# nbiot_gps.net
KiCad netlist of a schematic drawn in Altium Designer
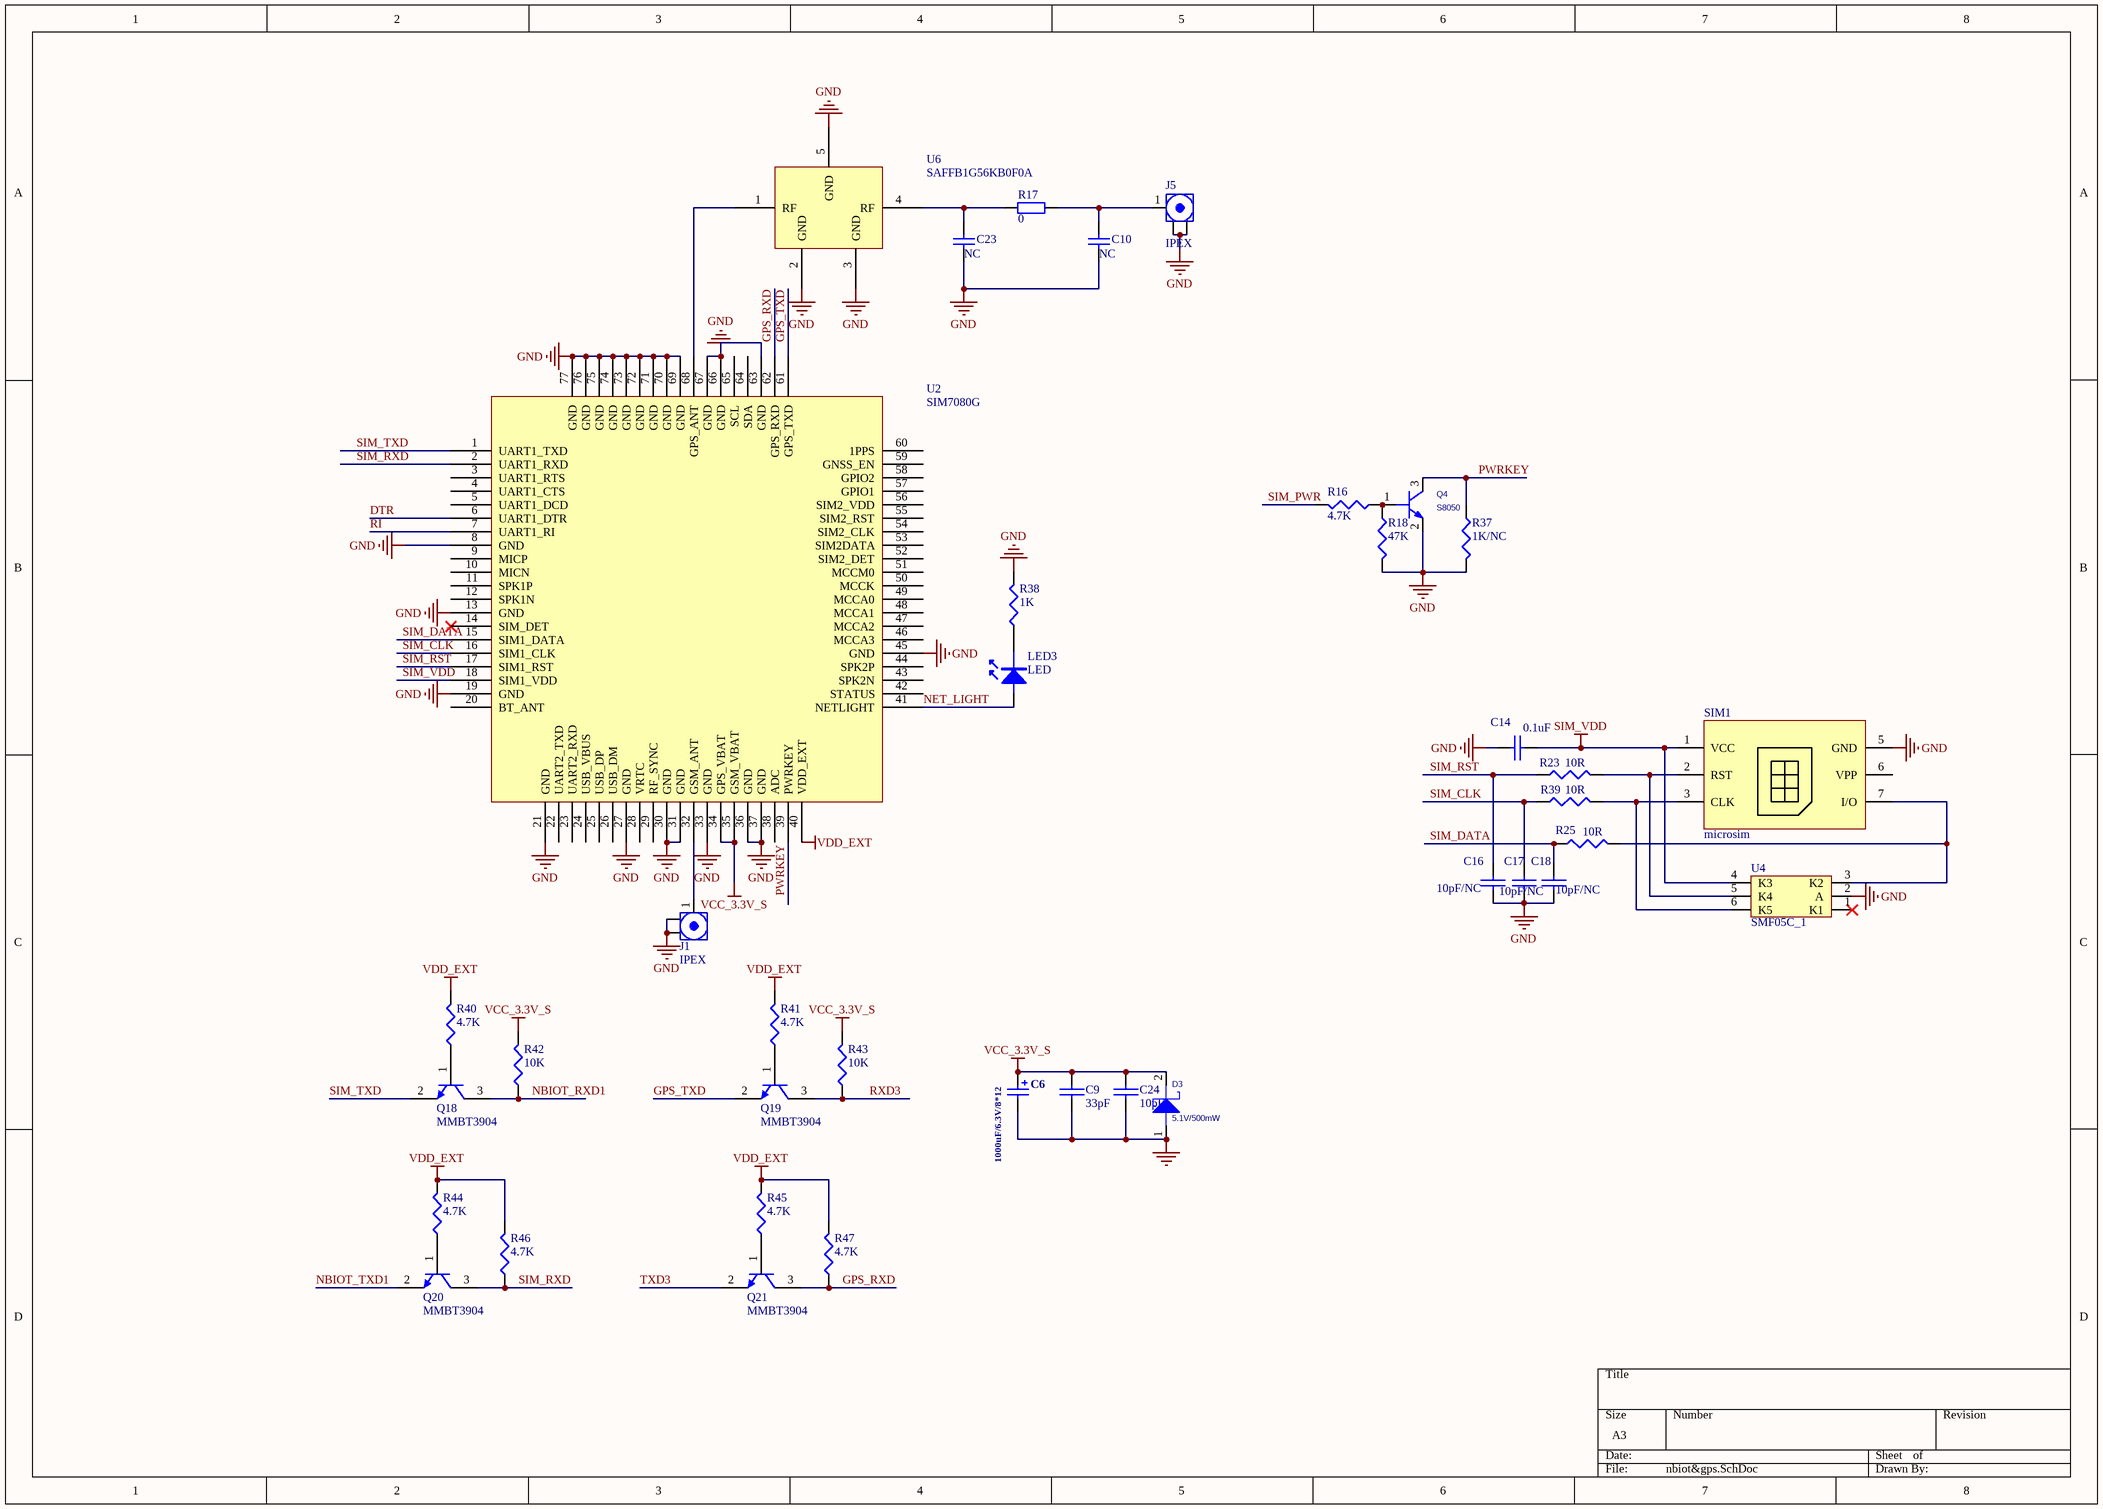
[diagram p0: nbiot&gps.SchDoc]

(export (version "E")
  (design (tool "Eeschema 10.0.6"))
  (components
    (comp (ref "C6")
      (value "1000uF/6.3V/8*12")
      (footprint "8*12")
      (description "Polarized Capacitor (Surface Mount)")
      (libsource (lib "KT_iBeacon") (part "Cap Pol3"))
    )
    (comp (ref "C9")
      (value "33pF")
      (footprint "0603C")
      (description "Capacitor")
      (libsource (lib "ZWLIntegrated_Library") (part "CAP"))
    )
    (comp (ref "C10")
      (value "NC")
      (footprint "0603C")
      (description "Capacitor")
      (fields (field (name "PUBLISHER") "Altium Limited"))
      (libsource (lib "Miscellaneous Devices") (part "Cap"))
    )
    (comp (ref "C14")
      (value "0.1uF")
      (footprint "0603C")
      (description "Capacitor")
      (libsource (lib "ZWLIntegrated_Library") (part "CAP"))
    )
    (comp (ref "C16")
      (value "10pF/NC")
      (footprint "0603C")
      (description "Capacitor")
      (libsource (lib "ZWLIntegrated_Library") (part "CAP"))
    )
    (comp (ref "C17")
      (value "10pF/NC")
      (footprint "0603C")
      (description "Capacitor")
      (libsource (lib "ZWLIntegrated_Library") (part "CAP"))
    )
    (comp (ref "C18")
      (value "10pF/NC")
      (footprint "0603C")
      (description "Capacitor")
      (libsource (lib "ZWLIntegrated_Library") (part "CAP"))
    )
    (comp (ref "C23")
      (value "NC")
      (footprint "0603C")
      (description "Capacitor")
      (fields (field (name "PUBLISHER") "Altium Limited"))
      (libsource (lib "Miscellaneous Devices") (part "Cap"))
    )
    (comp (ref "C24")
      (value "10pF")
      (footprint "0603C")
      (description "Capacitor")
      (libsource (lib "ZWLIntegrated_Library") (part "CAP"))
    )
    (comp (ref "D3")
      (value "5.1V/500mW")
      (footprint "LL-34(D1206)")
      (fields (field (name "Comment") "DIODE_SCHOTTKY_0"))
      (libsource (lib "KT_iBeacon") (part "DIODE_SCHOTTKY_0"))
    )
    (comp (ref "J1") (value "IPEX") (footprint "RF-UFL") (libsource (lib "我的元件库") (part "ANT")))
    (comp (ref "J5") (value "IPEX") (footprint "RF-UFL") (libsource (lib "我的元件库") (part "ANT")))
    (comp (ref "LED3") (value "LED") (footprint "0603LED") (libsource (lib "我的元件库") (part "LED")))
    (comp (ref "Q4") (value "S8050") (footprint "SOT23") (libsource (lib "*") (part "2N1069_1")))
    (comp (ref "Q18") (value "MMBT3904") (footprint "SOT23-3") (libsource (lib "Schlib1") (part "NPN")))
    (comp (ref "Q19") (value "MMBT3904") (footprint "SOT23-3") (libsource (lib "Schlib1") (part "NPN")))
    (comp (ref "Q20") (value "MMBT3904") (footprint "SOT23-3") (libsource (lib "Schlib1") (part "NPN")))
    (comp (ref "Q21") (value "MMBT3904") (footprint "SOT23-3") (libsource (lib "Schlib1") (part "NPN")))
    (comp (ref "R16")
      (value "4.7K")
      (footprint "0603R")
      (libsource (lib "ZWLIntegrated_Library") (part "RES1"))
    )
    (comp (ref "R17")
      (value "0")
      (footprint "0603R")
      (description "Resistor")
      (fields (field (name "PUBLISHER") "Altium Limited"))
      (libsource (lib "Miscellaneous Devices") (part "Res2"))
    )
    (comp (ref "R18")
      (value "47K")
      (footprint "0603R")
      (libsource (lib "ZWLIntegrated_Library") (part "RES1"))
    )
    (comp (ref "R23")
      (value "10R")
      (footprint "0603R")
      (libsource (lib "ZWLIntegrated_Library") (part "RES1"))
    )
    (comp (ref "R25")
      (value "10R")
      (footprint "0603R")
      (libsource (lib "ZWLIntegrated_Library") (part "RES1"))
    )
    (comp (ref "R37")
      (value "1K/NC")
      (footprint "0603R")
      (libsource (lib "ZWLIntegrated_Library") (part "RES1"))
    )
    (comp (ref "R38")
      (value "1K")
      (footprint "0603R")
      (libsource (lib "ZWLIntegrated_Library") (part "RES1"))
    )
    (comp (ref "R39")
      (value "10R")
      (footprint "0603R")
      (libsource (lib "ZWLIntegrated_Library") (part "RES1"))
    )
    (comp (ref "R40")
      (value "4.7K")
      (footprint "0603R")
      (libsource (lib "ZWLIntegrated_Library") (part "RES1"))
    )
    (comp (ref "R41")
      (value "4.7K")
      (footprint "0603R")
      (libsource (lib "ZWLIntegrated_Library") (part "RES1"))
    )
    (comp (ref "R42")
      (value "10K")
      (footprint "0603R")
      (libsource (lib "ZWLIntegrated_Library") (part "RES1"))
    )
    (comp (ref "R43")
      (value "10K")
      (footprint "0603R")
      (libsource (lib "ZWLIntegrated_Library") (part "RES1"))
    )
    (comp (ref "R44")
      (value "4.7K")
      (footprint "0603R")
      (libsource (lib "ZWLIntegrated_Library") (part "RES1"))
    )
    (comp (ref "R45")
      (value "4.7K")
      (footprint "0603R")
      (libsource (lib "ZWLIntegrated_Library") (part "RES1"))
    )
    (comp (ref "R46")
      (value "4.7K")
      (footprint "0603R")
      (libsource (lib "ZWLIntegrated_Library") (part "RES1"))
    )
    (comp (ref "R47")
      (value "4.7K")
      (footprint "0603R")
      (libsource (lib "ZWLIntegrated_Library") (part "RES1"))
    )
    (comp (ref "SIM1")
      (value "microsim")
      (footprint "Nano SIM")
      (libsource (lib "SIM800C 原理图库") (part "microsim"))
    )
    (comp (ref "U2")
      (value "SIM7080G")
      (footprint "SIM868")
      (libsource (lib "stm32") (part "SIM868E/SIM868"))
    )
    (comp (ref "U4")
      (value "SMF05C_1")
      (footprint "SC70-6L")
      (description "TVS")
      (libsource (lib "SIM800C 原理图库") (part "SMF05C_1"))
    )
    (comp (ref "U6")
      (value "SAFFB1G56KB0F0A")
      (footprint "SAFFB1G56KB0F0A")
      (libsource (lib "stm32") (part "SAFFB1G56KBOFA"))
    )
  )
  (nets
    (net (code "1") (name "/DTR") (class "Default")
      (node (ref "U2") (pin "6") (pinfunction "UART1_DTR_6") (pintype "passive"))
    )
    (net (code "2") (name "/GPS_RXD") (class "Default")
      (node (ref "Q21") (pin "3") (pinfunction "C_3") (pintype "passive"))
      (node (ref "R47") (pin "1") (pinfunction "1_1") (pintype "passive"))
      (node (ref "U2") (pin "62") (pinfunction "GPS_RXD_62") (pintype "passive"))
    )
    (net (code "3") (name "/GPS_TXD") (class "Default")
      (node (ref "Q19") (pin "2") (pinfunction "E_2") (pintype "passive"))
      (node (ref "U2") (pin "61") (pinfunction "GPS_TXD_61") (pintype "passive"))
    )
    (net (code "4") (name "/NBIOT_RXD1") (class "Default")
      (node (ref "Q18") (pin "3") (pinfunction "C_3") (pintype "passive"))
      (node (ref "R42") (pin "1") (pinfunction "1_1") (pintype "passive"))
    )
    (net (code "5") (name "/NBIOT_TXD1") (class "Default")
      (node (ref "Q20") (pin "2") (pinfunction "E_2") (pintype "passive"))
    )
    (net (code "6") (name "/NET_LIGHT") (class "Default")
      (node (ref "LED3") (pin "1") (pinfunction "1_1") (pintype "passive"))
      (node (ref "U2") (pin "41") (pinfunction "NETLIGHT_41") (pintype "passive"))
    )
    (net (code "7") (name "/PWRKEY") (class "Default")
      (node (ref "Q4") (pin "3") (pinfunction "C_3") (pintype "passive"))
      (node (ref "R37") (pin "1") (pinfunction "1_1") (pintype "passive"))
      (node (ref "U2") (pin "39") (pinfunction "PWRKEY_39") (pintype "passive"))
    )
    (net (code "8") (name "/RI") (class "Default")
      (node (ref "U2") (pin "7") (pinfunction "UART1_RI_7") (pintype "passive"))
    )
    (net (code "9") (name "/RXD3") (class "Default")
      (node (ref "Q19") (pin "3") (pinfunction "C_3") (pintype "passive"))
      (node (ref "R43") (pin "1") (pinfunction "1_1") (pintype "passive"))
    )
    (net (code "10") (name "/SIM_CLK") (class "Default")
      (node (ref "C17") (pin "2") (pinfunction "2_2") (pintype "passive"))
      (node (ref "R39") (pin "1") (pinfunction "1_1") (pintype "passive"))
      (node (ref "U2") (pin "16") (pinfunction "SIM1_CLK_16") (pintype "passive"))
    )
    (net (code "11") (name "/SIM_DATA") (class "Default")
      (node (ref "C18") (pin "2") (pinfunction "2_2") (pintype "passive"))
      (node (ref "R25") (pin "1") (pinfunction "1_1") (pintype "passive"))
      (node (ref "U2") (pin "15") (pinfunction "SIM1_DATA_15") (pintype "passive"))
    )
    (net (code "12") (name "/SIM_PWR") (class "Default")
      (node (ref "R16") (pin "2") (pinfunction "2_2") (pintype "passive"))
    )
    (net (code "13") (name "/SIM_RST") (class "Default")
      (node (ref "C16") (pin "2") (pinfunction "2_2") (pintype "passive"))
      (node (ref "R23") (pin "1") (pinfunction "1_1") (pintype "passive"))
      (node (ref "U2") (pin "17") (pinfunction "SIM1_RST_17") (pintype "passive"))
    )
    (net (code "14") (name "/SIM_RXD") (class "Default")
      (node (ref "Q20") (pin "3") (pinfunction "C_3") (pintype "passive"))
      (node (ref "R46") (pin "1") (pinfunction "1_1") (pintype "passive"))
      (node (ref "U2") (pin "2") (pinfunction "UART1_RXD_2") (pintype "passive"))
    )
    (net (code "15") (name "/SIM_TXD") (class "Default")
      (node (ref "Q18") (pin "2") (pinfunction "E_2") (pintype "passive"))
      (node (ref "U2") (pin "1") (pinfunction "UART1_TXD_1") (pintype "passive"))
    )
    (net (code "16") (name "/TXD3") (class "Default")
      (node (ref "Q21") (pin "2") (pinfunction "E_2") (pintype "passive"))
    )
    (net (code "17") (name "GND") (class "Default")
      (node (ref "C10") (pin "2") (pinfunction "2_2") (pintype "passive"))
      (node (ref "C14") (pin "1") (pinfunction "1_1") (pintype "passive"))
      (node (ref "C16") (pin "1") (pinfunction "1_1") (pintype "passive"))
      (node (ref "C17") (pin "1") (pinfunction "1_1") (pintype "passive"))
      (node (ref "C18") (pin "1") (pinfunction "1_1") (pintype "passive"))
      (node (ref "C23") (pin "2") (pinfunction "2_2") (pintype "passive"))
      (node (ref "C24") (pin "1") (pinfunction "1_1") (pintype "passive"))
      (node (ref "C6") (pin "2") (pinfunction "2_2") (pintype "passive"))
      (node (ref "C9") (pin "1") (pinfunction "1_1") (pintype "passive"))
      (node (ref "D3") (pin "1") (pinfunction "1_1") (pintype "passive"))
      (node (ref "J1") (pin "2") (pinfunction "Y_2") (pintype "passive"))
      (node (ref "J5") (pin "2") (pinfunction "Y_2") (pintype "passive"))
      (node (ref "Q4") (pin "2") (pinfunction "E_2") (pintype "passive"))
      (node (ref "R18") (pin "2") (pinfunction "2_2") (pintype "passive"))
      (node (ref "R37") (pin "2") (pinfunction "2_2") (pintype "passive"))
      (node (ref "R38") (pin "2") (pinfunction "2_2") (pintype "passive"))
      (node (ref "SIM1") (pin "5") (pinfunction "GND_5") (pintype "passive"))
      (node (ref "U2") (pin "13") (pinfunction "GND_13") (pintype "passive"))
      (node (ref "U2") (pin "19") (pinfunction "GND_19") (pintype "passive"))
      (node (ref "U2") (pin "21") (pinfunction "GND_21") (pintype "passive"))
      (node (ref "U2") (pin "27") (pinfunction "GND_27") (pintype "passive"))
      (node (ref "U2") (pin "30") (pinfunction "GND_30") (pintype "passive"))
      (node (ref "U2") (pin "31") (pinfunction "GND_31") (pintype "passive"))
      (node (ref "U2") (pin "33") (pinfunction "GND_33") (pintype "passive"))
      (node (ref "U2") (pin "36") (pinfunction "GND_36") (pintype "passive"))
      (node (ref "U2") (pin "37") (pinfunction "GND_37") (pintype "passive"))
      (node (ref "U2") (pin "45") (pinfunction "GND_45") (pintype "passive"))
      (node (ref "U2") (pin "63") (pinfunction "GND_63") (pintype "passive"))
      (node (ref "U2") (pin "66") (pinfunction "GND_66") (pintype "passive"))
      (node (ref "U2") (pin "67") (pinfunction "GND_67") (pintype "passive"))
      (node (ref "U2") (pin "69") (pinfunction "GND_69") (pintype "passive"))
      (node (ref "U2") (pin "70") (pinfunction "GND_70") (pintype "passive"))
      (node (ref "U2") (pin "71") (pinfunction "GND_71") (pintype "passive"))
      (node (ref "U2") (pin "72") (pinfunction "GND_72") (pintype "passive"))
      (node (ref "U2") (pin "73") (pinfunction "GND_73") (pintype "passive"))
      (node (ref "U2") (pin "74") (pinfunction "GND_74") (pintype "passive"))
      (node (ref "U2") (pin "75") (pinfunction "GND_75") (pintype "passive"))
      (node (ref "U2") (pin "76") (pinfunction "GND_76") (pintype "passive"))
      (node (ref "U2") (pin "77") (pinfunction "GND_77") (pintype "passive"))
      (node (ref "U2") (pin "8") (pinfunction "GND_8") (pintype "passive"))
      (node (ref "U4") (pin "2") (pinfunction "A_2") (pintype "passive"))
      (node (ref "U6") (pin "2") (pinfunction "GND_2") (pintype "passive"))
      (node (ref "U6") (pin "3") (pinfunction "GND_3") (pintype "passive"))
      (node (ref "U6") (pin "5") (pinfunction "GND_5") (pintype "passive"))
    )
    (net (code "18") (name "Net-(C23-Pad1)") (class "Default")
      (node (ref "C23") (pin "1") (pinfunction "1_1") (pintype "passive"))
      (node (ref "R17") (pin "1") (pinfunction "1_1") (pintype "passive"))
      (node (ref "U6") (pin "4") (pinfunction "RF_4") (pintype "passive"))
    )
    (net (code "19") (name "Net-(J1-X)") (class "Default")
      (node (ref "J1") (pin "1") (pinfunction "X_1") (pintype "passive"))
      (node (ref "U2") (pin "32") (pinfunction "GSM_ANT_32") (pintype "passive"))
    )
    (net (code "20") (name "Net-(J5-X)") (class "Default")
      (node (ref "C10") (pin "1") (pinfunction "1_1") (pintype "passive"))
      (node (ref "J5") (pin "1") (pinfunction "X_1") (pintype "passive"))
      (node (ref "R17") (pin "2") (pinfunction "2_2") (pintype "passive"))
    )
    (net (code "21") (name "Net-(LED3-Pad2)") (class "Default")
      (node (ref "LED3") (pin "2") (pinfunction "2_2") (pintype "passive"))
      (node (ref "R38") (pin "1") (pinfunction "1_1") (pintype "passive"))
    )
    (net (code "22") (name "Net-(Q4-B)") (class "Default")
      (node (ref "Q4") (pin "1") (pinfunction "B_1") (pintype "passive"))
      (node (ref "R16") (pin "1") (pinfunction "1_1") (pintype "passive"))
      (node (ref "R18") (pin "1") (pinfunction "1_1") (pintype "passive"))
    )
    (net (code "23") (name "Net-(Q18-B)") (class "Default")
      (node (ref "Q18") (pin "1") (pinfunction "B_1") (pintype "passive"))
      (node (ref "R40") (pin "1") (pinfunction "1_1") (pintype "passive"))
    )
    (net (code "24") (name "Net-(Q19-B)") (class "Default")
      (node (ref "Q19") (pin "1") (pinfunction "B_1") (pintype "passive"))
      (node (ref "R41") (pin "1") (pinfunction "1_1") (pintype "passive"))
    )
    (net (code "25") (name "Net-(Q20-B)") (class "Default")
      (node (ref "Q20") (pin "1") (pinfunction "B_1") (pintype "passive"))
      (node (ref "R44") (pin "1") (pinfunction "1_1") (pintype "passive"))
    )
    (net (code "26") (name "Net-(Q21-B)") (class "Default")
      (node (ref "Q21") (pin "1") (pinfunction "B_1") (pintype "passive"))
      (node (ref "R45") (pin "1") (pinfunction "1_1") (pintype "passive"))
    )
    (net (code "27") (name "Net-(SIM1-CLK)") (class "Default")
      (node (ref "R39") (pin "2") (pinfunction "2_2") (pintype "passive"))
      (node (ref "SIM1") (pin "3") (pinfunction "CLK_3") (pintype "passive"))
      (node (ref "U4") (pin "6") (pinfunction "K5_6") (pintype "passive"))
    )
    (net (code "28") (name "Net-(SIM1-I{slash}O)") (class "Default")
      (node (ref "R25") (pin "2") (pinfunction "2_2") (pintype "passive"))
      (node (ref "SIM1") (pin "7") (pinfunction "I/O_7") (pintype "passive"))
      (node (ref "U4") (pin "3") (pinfunction "K2_3") (pintype "passive"))
    )
    (net (code "29") (name "Net-(SIM1-RST)") (class "Default")
      (node (ref "R23") (pin "2") (pinfunction "2_2") (pintype "passive"))
      (node (ref "SIM1") (pin "2") (pinfunction "RST_2") (pintype "passive"))
      (node (ref "U4") (pin "5") (pinfunction "K4_5") (pintype "passive"))
    )
    (net (code "30") (name "Net-(U2-GPS_ANT)") (class "Default")
      (node (ref "U2") (pin "68") (pinfunction "GPS_ANT_68") (pintype "passive"))
      (node (ref "U6") (pin "1") (pinfunction "RF_1") (pintype "passive"))
    )
    (net (code "31") (name "SIM_VDD") (class "Default")
      (node (ref "C14") (pin "2") (pinfunction "2_2") (pintype "passive"))
      (node (ref "SIM1") (pin "1") (pinfunction "VCC_1") (pintype "passive"))
      (node (ref "U2") (pin "18") (pinfunction "SIM1_VDD_18") (pintype "passive"))
      (node (ref "U4") (pin "4") (pinfunction "K3_4") (pintype "passive"))
    )
    (net (code "32") (name "VCC_3.3V_S") (class "Default")
      (node (ref "C24") (pin "2") (pinfunction "2_2") (pintype "passive"))
      (node (ref "C6") (pin "1") (pinfunction "1_1") (pintype "passive"))
      (node (ref "C9") (pin "2") (pinfunction "2_2") (pintype "passive"))
      (node (ref "D3") (pin "2") (pinfunction "2_2") (pintype "passive"))
      (node (ref "R42") (pin "2") (pinfunction "2_2") (pintype "passive"))
      (node (ref "R43") (pin "2") (pinfunction "2_2") (pintype "passive"))
      (node (ref "U2") (pin "34") (pinfunction "GPS_VBAT_34") (pintype "passive"))
      (node (ref "U2") (pin "35") (pinfunction "GSM_VBAT_35") (pintype "passive"))
    )
    (net (code "33") (name "VDD_EXT") (class "Default")
      (node (ref "R40") (pin "2") (pinfunction "2_2") (pintype "passive"))
      (node (ref "R41") (pin "2") (pinfunction "2_2") (pintype "passive"))
      (node (ref "R44") (pin "2") (pinfunction "2_2") (pintype "passive"))
      (node (ref "R45") (pin "2") (pinfunction "2_2") (pintype "passive"))
      (node (ref "R46") (pin "2") (pinfunction "2_2") (pintype "passive"))
      (node (ref "R47") (pin "2") (pinfunction "2_2") (pintype "passive"))
      (node (ref "U2") (pin "40") (pinfunction "VDD_EXT_40") (pintype "passive"))
    )
    (net (code "34") (name "unconnected-(SIM1-VPP-Pad6)") (class "Default")
      (node (ref "SIM1") (pin "6") (pinfunction "VPP_6") (pintype "passive"))
    )
    (net (code "35") (name "unconnected-(U2-1PPS-Pad60)") (class "Default")
      (node (ref "U2") (pin "60") (pinfunction "1PPS_60") (pintype "passive"))
    )
    (net (code "36") (name "unconnected-(U2-ADC-Pad38)") (class "Default")
      (node (ref "U2") (pin "38") (pinfunction "ADC_38") (pintype "passive"))
    )
    (net (code "37") (name "unconnected-(U2-BT_ANT-Pad20)") (class "Default")
      (node (ref "U2") (pin "20") (pinfunction "BT_ANT_20") (pintype "passive"))
    )
    (net (code "38") (name "unconnected-(U2-GNSS_EN-Pad59)") (class "Default")
      (node (ref "U2") (pin "59") (pinfunction "GNSS_EN_59") (pintype "passive"))
    )
    (net (code "39") (name "unconnected-(U2-GPIO1-Pad57)") (class "Default")
      (node (ref "U2") (pin "57") (pinfunction "GPIO1_57") (pintype "passive"))
    )
    (net (code "40") (name "unconnected-(U2-GPIO2-Pad58)") (class "Default")
      (node (ref "U2") (pin "58") (pinfunction "GPIO2_58") (pintype "passive"))
    )
    (net (code "41") (name "unconnected-(U2-MCCA0-Pad49)") (class "Default")
      (node (ref "U2") (pin "49") (pinfunction "MCCA0_49") (pintype "passive"))
    )
    (net (code "42") (name "unconnected-(U2-MCCA1-Pad48)") (class "Default")
      (node (ref "U2") (pin "48") (pinfunction "MCCA1_48") (pintype "passive"))
    )
    (net (code "43") (name "unconnected-(U2-MCCA2-Pad47)") (class "Default")
      (node (ref "U2") (pin "47") (pinfunction "MCCA2_47") (pintype "passive"))
    )
    (net (code "44") (name "unconnected-(U2-MCCA3-Pad46)") (class "Default")
      (node (ref "U2") (pin "46") (pinfunction "MCCA3_46") (pintype "passive"))
    )
    (net (code "45") (name "unconnected-(U2-MCCK-Pad50)") (class "Default")
      (node (ref "U2") (pin "50") (pinfunction "MCCK_50") (pintype "passive"))
    )
    (net (code "46") (name "unconnected-(U2-MCCM0-Pad51)") (class "Default")
      (node (ref "U2") (pin "51") (pinfunction "MCCM0_51") (pintype "passive"))
    )
    (net (code "47") (name "unconnected-(U2-MICN-Pad10)") (class "Default")
      (node (ref "U2") (pin "10") (pinfunction "MICN_10") (pintype "passive"))
    )
    (net (code "48") (name "unconnected-(U2-MICP-Pad9)") (class "Default")
      (node (ref "U2") (pin "9") (pinfunction "MICP_9") (pintype "passive"))
    )
    (net (code "49") (name "unconnected-(U2-RF_SYNC-Pad29)") (class "Default")
      (node (ref "U2") (pin "29") (pinfunction "RF_SYNC_29") (pintype "passive"))
    )
    (net (code "50") (name "unconnected-(U2-SCL-Pad65)") (class "Default")
      (node (ref "U2") (pin "65") (pinfunction "SCL_65") (pintype "passive"))
    )
    (net (code "51") (name "unconnected-(U2-SDA-Pad64)") (class "Default")
      (node (ref "U2") (pin "64") (pinfunction "SDA_64") (pintype "passive"))
    )
    (net (code "52") (name "unconnected-(U2-SIM2DATA-Pad53)") (class "Default")
      (node (ref "U2") (pin "53") (pinfunction "SIM2DATA_53") (pintype "passive"))
    )
    (net (code "53") (name "unconnected-(U2-SIM2_CLK-Pad54)") (class "Default")
      (node (ref "U2") (pin "54") (pinfunction "SIM2_CLK_54") (pintype "passive"))
    )
    (net (code "54") (name "unconnected-(U2-SIM2_DET-Pad52)") (class "Default")
      (node (ref "U2") (pin "52") (pinfunction "SIM2_DET_52") (pintype "passive"))
    )
    (net (code "55") (name "unconnected-(U2-SIM2_RST-Pad55)") (class "Default")
      (node (ref "U2") (pin "55") (pinfunction "SIM2_RST_55") (pintype "passive"))
    )
    (net (code "56") (name "unconnected-(U2-SIM2_VDD-Pad56)") (class "Default")
      (node (ref "U2") (pin "56") (pinfunction "SIM2_VDD_56") (pintype "passive"))
    )
    (net (code "57") (name "unconnected-(U2-SIM_DET-Pad14)") (class "Default")
      (node (ref "U2") (pin "14") (pinfunction "SIM_DET_14") (pintype "passive+no_connect"))
    )
    (net (code "58") (name "unconnected-(U2-SPK1N-Pad12)") (class "Default")
      (node (ref "U2") (pin "12") (pinfunction "SPK1N_12") (pintype "passive"))
    )
    (net (code "59") (name "unconnected-(U2-SPK1P-Pad11)") (class "Default")
      (node (ref "U2") (pin "11") (pinfunction "SPK1P_11") (pintype "passive"))
    )
    (net (code "60") (name "unconnected-(U2-SPK2N-Pad43)") (class "Default")
      (node (ref "U2") (pin "43") (pinfunction "SPK2N_43") (pintype "passive"))
    )
    (net (code "61") (name "unconnected-(U2-SPK2P-Pad44)") (class "Default")
      (node (ref "U2") (pin "44") (pinfunction "SPK2P_44") (pintype "passive"))
    )
    (net (code "62") (name "unconnected-(U2-STATUS-Pad42)") (class "Default")
      (node (ref "U2") (pin "42") (pinfunction "STATUS_42") (pintype "passive"))
    )
    (net (code "63") (name "unconnected-(U2-UART1_CTS-Pad4)") (class "Default")
      (node (ref "U2") (pin "4") (pinfunction "UART1_CTS_4") (pintype "passive"))
    )
    (net (code "64") (name "unconnected-(U2-UART1_DCD-Pad5)") (class "Default")
      (node (ref "U2") (pin "5") (pinfunction "UART1_DCD_5") (pintype "passive"))
    )
    (net (code "65") (name "unconnected-(U2-UART1_RTS-Pad3)") (class "Default")
      (node (ref "U2") (pin "3") (pinfunction "UART1_RTS_3") (pintype "passive"))
    )
    (net (code "66") (name "unconnected-(U2-UART2_RXD-Pad23)") (class "Default")
      (node (ref "U2") (pin "23") (pinfunction "UART2_RXD_23") (pintype "passive"))
    )
    (net (code "67") (name "unconnected-(U2-UART2_TXD-Pad22)") (class "Default")
      (node (ref "U2") (pin "22") (pinfunction "UART2_TXD_22") (pintype "passive"))
    )
    (net (code "68") (name "unconnected-(U2-USB_DM-Pad26)") (class "Default")
      (node (ref "U2") (pin "26") (pinfunction "USB_DM_26") (pintype "passive"))
    )
    (net (code "69") (name "unconnected-(U2-USB_DP-Pad25)") (class "Default")
      (node (ref "U2") (pin "25") (pinfunction "USB_DP_25") (pintype "passive"))
    )
    (net (code "70") (name "unconnected-(U2-USB_VBUS-Pad24)") (class "Default")
      (node (ref "U2") (pin "24") (pinfunction "USB_VBUS_24") (pintype "passive"))
    )
    (net (code "71") (name "unconnected-(U2-VRTC-Pad28)") (class "Default")
      (node (ref "U2") (pin "28") (pinfunction "VRTC_28") (pintype "passive"))
    )
    (net (code "72") (name "unconnected-(U4-K1-Pad1)") (class "Default")
      (node (ref "U4") (pin "1") (pinfunction "K1_1") (pintype "passive+no_connect"))
    )
  )
)
